# Power_ATX.net
KiCad netlist of a schematic drawn in Altium Designer
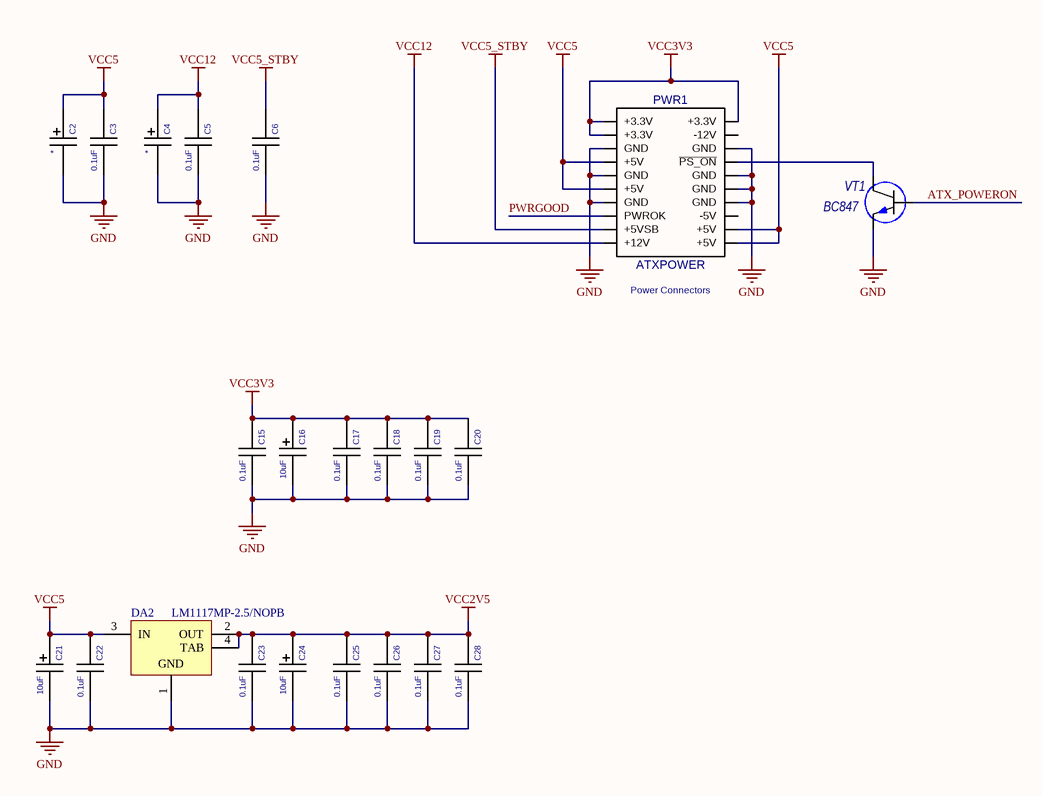
[diagram p0: Power ATX.SchDoc]

(export (version "E")
  (design (tool "Eeschema 10.0.6"))
  (components
    (comp (ref "C2")
      (value "ECAPCHIPB")
      (footprint "EC-CHIPB")
      (fields (field (name "ALTIUM_VALUE") "*"))
      (libsource (lib "zxevo") (part "ECAPCHIPB"))
    )
    (comp (ref "C3")
      (value "0.1uF")
      (footprint "C-CHIP")
      (description "CAPCHIP")
      (libsource (lib "*") (part "CAPCHIP"))
    )
    (comp (ref "C4")
      (value "ECAPCHIPB")
      (footprint "EC-CHIPB")
      (fields (field (name "ALTIUM_VALUE") "*"))
      (libsource (lib "zxevo") (part "ECAPCHIPB"))
    )
    (comp (ref "C5")
      (value "0.1uF")
      (footprint "C-CHIP")
      (description "CAPCHIP")
      (libsource (lib "*") (part "CAPCHIP"))
    )
    (comp (ref "C6")
      (value "0.1uF")
      (footprint "C-CHIP")
      (description "CAPCHIP")
      (libsource (lib "*") (part "CAPCHIP"))
    )
    (comp (ref "C15")
      (value "0.1uF")
      (footprint "C-CHIP")
      (description "CAPCHIP")
      (libsource (lib "*") (part "CAPCHIP"))
    )
    (comp (ref "C16")
      (value "10uF")
      (footprint "EC-CHIP")
      (description "ECAPCHIP")
      (libsource (lib "*") (part "ECAPCHIP"))
    )
    (comp (ref "C17")
      (value "0.1uF")
      (footprint "C-CHIP")
      (description "CAPCHIP")
      (libsource (lib "*") (part "CAPCHIP"))
    )
    (comp (ref "C18")
      (value "0.1uF")
      (footprint "C-CHIP")
      (description "CAPCHIP")
      (libsource (lib "*") (part "CAPCHIP"))
    )
    (comp (ref "C19")
      (value "0.1uF")
      (footprint "C-CHIP")
      (description "CAPCHIP")
      (libsource (lib "*") (part "CAPCHIP"))
    )
    (comp (ref "C20")
      (value "0.1uF")
      (footprint "C-CHIP")
      (description "CAPCHIP")
      (libsource (lib "*") (part "CAPCHIP"))
    )
    (comp (ref "C21")
      (value "10uF")
      (footprint "EC-CHIP")
      (description "ECAPCHIP")
      (libsource (lib "*") (part "ECAPCHIP"))
    )
    (comp (ref "C22")
      (value "0.1uF")
      (footprint "C-CHIP")
      (description "CAPCHIP")
      (libsource (lib "*") (part "CAPCHIP"))
    )
    (comp (ref "C23")
      (value "0.1uF")
      (footprint "C-CHIP")
      (description "CAPCHIP")
      (libsource (lib "*") (part "CAPCHIP"))
    )
    (comp (ref "C24")
      (value "10uF")
      (footprint "EC-CHIP")
      (description "ECAPCHIP")
      (libsource (lib "*") (part "ECAPCHIP"))
    )
    (comp (ref "C25")
      (value "0.1uF")
      (footprint "C-CHIP")
      (description "CAPCHIP")
      (libsource (lib "*") (part "CAPCHIP"))
    )
    (comp (ref "C26")
      (value "0.1uF")
      (footprint "C-CHIP")
      (description "CAPCHIP")
      (libsource (lib "*") (part "CAPCHIP"))
    )
    (comp (ref "C27")
      (value "0.1uF")
      (footprint "C-CHIP")
      (description "CAPCHIP")
      (libsource (lib "*") (part "CAPCHIP"))
    )
    (comp (ref "C28")
      (value "0.1uF")
      (footprint "C-CHIP")
      (description "CAPCHIP")
      (libsource (lib "*") (part "CAPCHIP"))
    )
    (comp (ref "DA2")
      (value "LM1117MP-2.5/NOPB")
      (footprint "DCY0004A_M")
      (description "800mA Low-Dropout Linear Regulator, 4-pin SOT-223, Pb-Free")
      (fields (field (name "MANUFACTURER") "Texas Instruments"))
      (libsource (lib "Altium Content Vault") (part "PM-REG-LM1086-SOT4"))
    )
    (comp (ref "PWR1") (value "ATXPOWER") (footprint "ATXPOWER") (libsource (lib "*") (part "ATXPOWER")))
    (comp (ref "VT1") (value "BC847") (footprint "SOT-23") (libsource (lib "*") (part "BC847")))
  )
  (nets
    (net (code "1") (name "/ATX_POWERON") (class "Default")
      (node (ref "VT1") (pin "1") (pinfunction "base_1") (pintype "passive"))
    )
    (net (code "2") (name "/PWRGOOD") (class "Default")
      (node (ref "PWR1") (pin "8") (pinfunction "PWROK_8") (pintype "passive"))
    )
    (net (code "3") (name "GND") (class "Default")
      (node (ref "C15") (pin "2") (pinfunction "2_2") (pintype "passive"))
      (node (ref "C16") (pin "2") (pintype "passive"))
      (node (ref "C17") (pin "2") (pinfunction "2_2") (pintype "passive"))
      (node (ref "C18") (pin "2") (pinfunction "2_2") (pintype "passive"))
      (node (ref "C19") (pin "2") (pinfunction "2_2") (pintype "passive"))
      (node (ref "C2") (pin "2") (pintype "passive"))
      (node (ref "C20") (pin "2") (pinfunction "2_2") (pintype "passive"))
      (node (ref "C21") (pin "2") (pintype "passive"))
      (node (ref "C22") (pin "2") (pinfunction "2_2") (pintype "passive"))
      (node (ref "C23") (pin "2") (pinfunction "2_2") (pintype "passive"))
      (node (ref "C24") (pin "2") (pintype "passive"))
      (node (ref "C25") (pin "2") (pinfunction "2_2") (pintype "passive"))
      (node (ref "C26") (pin "2") (pinfunction "2_2") (pintype "passive"))
      (node (ref "C27") (pin "2") (pinfunction "2_2") (pintype "passive"))
      (node (ref "C28") (pin "2") (pinfunction "2_2") (pintype "passive"))
      (node (ref "C3") (pin "2") (pinfunction "2_2") (pintype "passive"))
      (node (ref "C4") (pin "2") (pintype "passive"))
      (node (ref "C5") (pin "2") (pinfunction "2_2") (pintype "passive"))
      (node (ref "C6") (pin "2") (pinfunction "2_2") (pintype "passive"))
      (node (ref "DA2") (pin "1") (pinfunction "GND_1") (pintype "power_in"))
      (node (ref "PWR1") (pin "13") (pinfunction "GND_13") (pintype "passive"))
      (node (ref "PWR1") (pin "15") (pinfunction "GND_15") (pintype "passive"))
      (node (ref "PWR1") (pin "16") (pinfunction "GND_16") (pintype "passive"))
      (node (ref "PWR1") (pin "17") (pinfunction "GND_17") (pintype "passive"))
      (node (ref "PWR1") (pin "3") (pinfunction "GND_3") (pintype "passive"))
      (node (ref "PWR1") (pin "5") (pinfunction "GND_5") (pintype "passive"))
      (node (ref "PWR1") (pin "7") (pinfunction "GND_7") (pintype "passive"))
      (node (ref "VT1") (pin "2") (pinfunction "emitter_2") (pintype "passive"))
    )
    (net (code "4") (name "Net-(PWR1-~{PS_ON})") (class "Default")
      (node (ref "PWR1") (pin "14") (pinfunction "~{PS_ON}_14") (pintype "passive"))
      (node (ref "VT1") (pin "3") (pinfunction "collector_3") (pintype "passive"))
    )
    (net (code "5") (name "VCC2V5") (class "Default")
      (node (ref "C23") (pin "1") (pinfunction "1_1") (pintype "passive"))
      (node (ref "C24") (pin "1") (pintype "passive"))
      (node (ref "C25") (pin "1") (pinfunction "1_1") (pintype "passive"))
      (node (ref "C26") (pin "1") (pinfunction "1_1") (pintype "passive"))
      (node (ref "C27") (pin "1") (pinfunction "1_1") (pintype "passive"))
      (node (ref "C28") (pin "1") (pinfunction "1_1") (pintype "passive"))
      (node (ref "DA2") (pin "2") (pinfunction "OUT_2") (pintype "power_in"))
      (node (ref "DA2") (pin "4") (pinfunction "TAB_4") (pintype "power_in"))
    )
    (net (code "6") (name "VCC3V3") (class "Default")
      (node (ref "C15") (pin "1") (pinfunction "1_1") (pintype "passive"))
      (node (ref "C16") (pin "1") (pintype "passive"))
      (node (ref "C17") (pin "1") (pinfunction "1_1") (pintype "passive"))
      (node (ref "C18") (pin "1") (pinfunction "1_1") (pintype "passive"))
      (node (ref "C19") (pin "1") (pinfunction "1_1") (pintype "passive"))
      (node (ref "C20") (pin "1") (pinfunction "1_1") (pintype "passive"))
      (node (ref "PWR1") (pin "1") (pinfunction "+3.3V_1") (pintype "passive"))
      (node (ref "PWR1") (pin "11") (pinfunction "+3.3V_11") (pintype "passive"))
      (node (ref "PWR1") (pin "2") (pinfunction "+3.3V_2") (pintype "passive"))
    )
    (net (code "7") (name "VCC5") (class "Default")
      (node (ref "C2") (pin "1") (pintype "passive"))
      (node (ref "C21") (pin "1") (pintype "passive"))
      (node (ref "C22") (pin "1") (pinfunction "1_1") (pintype "passive"))
      (node (ref "C3") (pin "1") (pinfunction "1_1") (pintype "passive"))
      (node (ref "DA2") (pin "3") (pinfunction "IN_3") (pintype "power_in"))
      (node (ref "PWR1") (pin "19") (pinfunction "+5V_19") (pintype "passive"))
      (node (ref "PWR1") (pin "20") (pinfunction "+5V_20") (pintype "passive"))
      (node (ref "PWR1") (pin "4") (pinfunction "+5V_4") (pintype "passive"))
      (node (ref "PWR1") (pin "6") (pinfunction "+5V_6") (pintype "passive"))
    )
    (net (code "8") (name "VCC5_STBY") (class "Default")
      (node (ref "C6") (pin "1") (pinfunction "1_1") (pintype "passive"))
      (node (ref "PWR1") (pin "9") (pinfunction "+5VSB_9") (pintype "passive"))
    )
    (net (code "9") (name "VCC12") (class "Default")
      (node (ref "C4") (pin "1") (pintype "passive"))
      (node (ref "C5") (pin "1") (pinfunction "1_1") (pintype "passive"))
      (node (ref "PWR1") (pin "10") (pinfunction "+12V_10") (pintype "passive"))
    )
    (net (code "10") (name "unconnected-(PWR1--5V-Pad18)") (class "Default")
      (node (ref "PWR1") (pin "18") (pinfunction "-5V_18") (pintype "passive"))
    )
    (net (code "11") (name "unconnected-(PWR1--12V-Pad12)") (class "Default")
      (node (ref "PWR1") (pin "12") (pinfunction "-12V_12") (pintype "passive"))
    )
  )
)
